# sensor-test.net
KiCad netlist of a schematic drawn in EAGLE
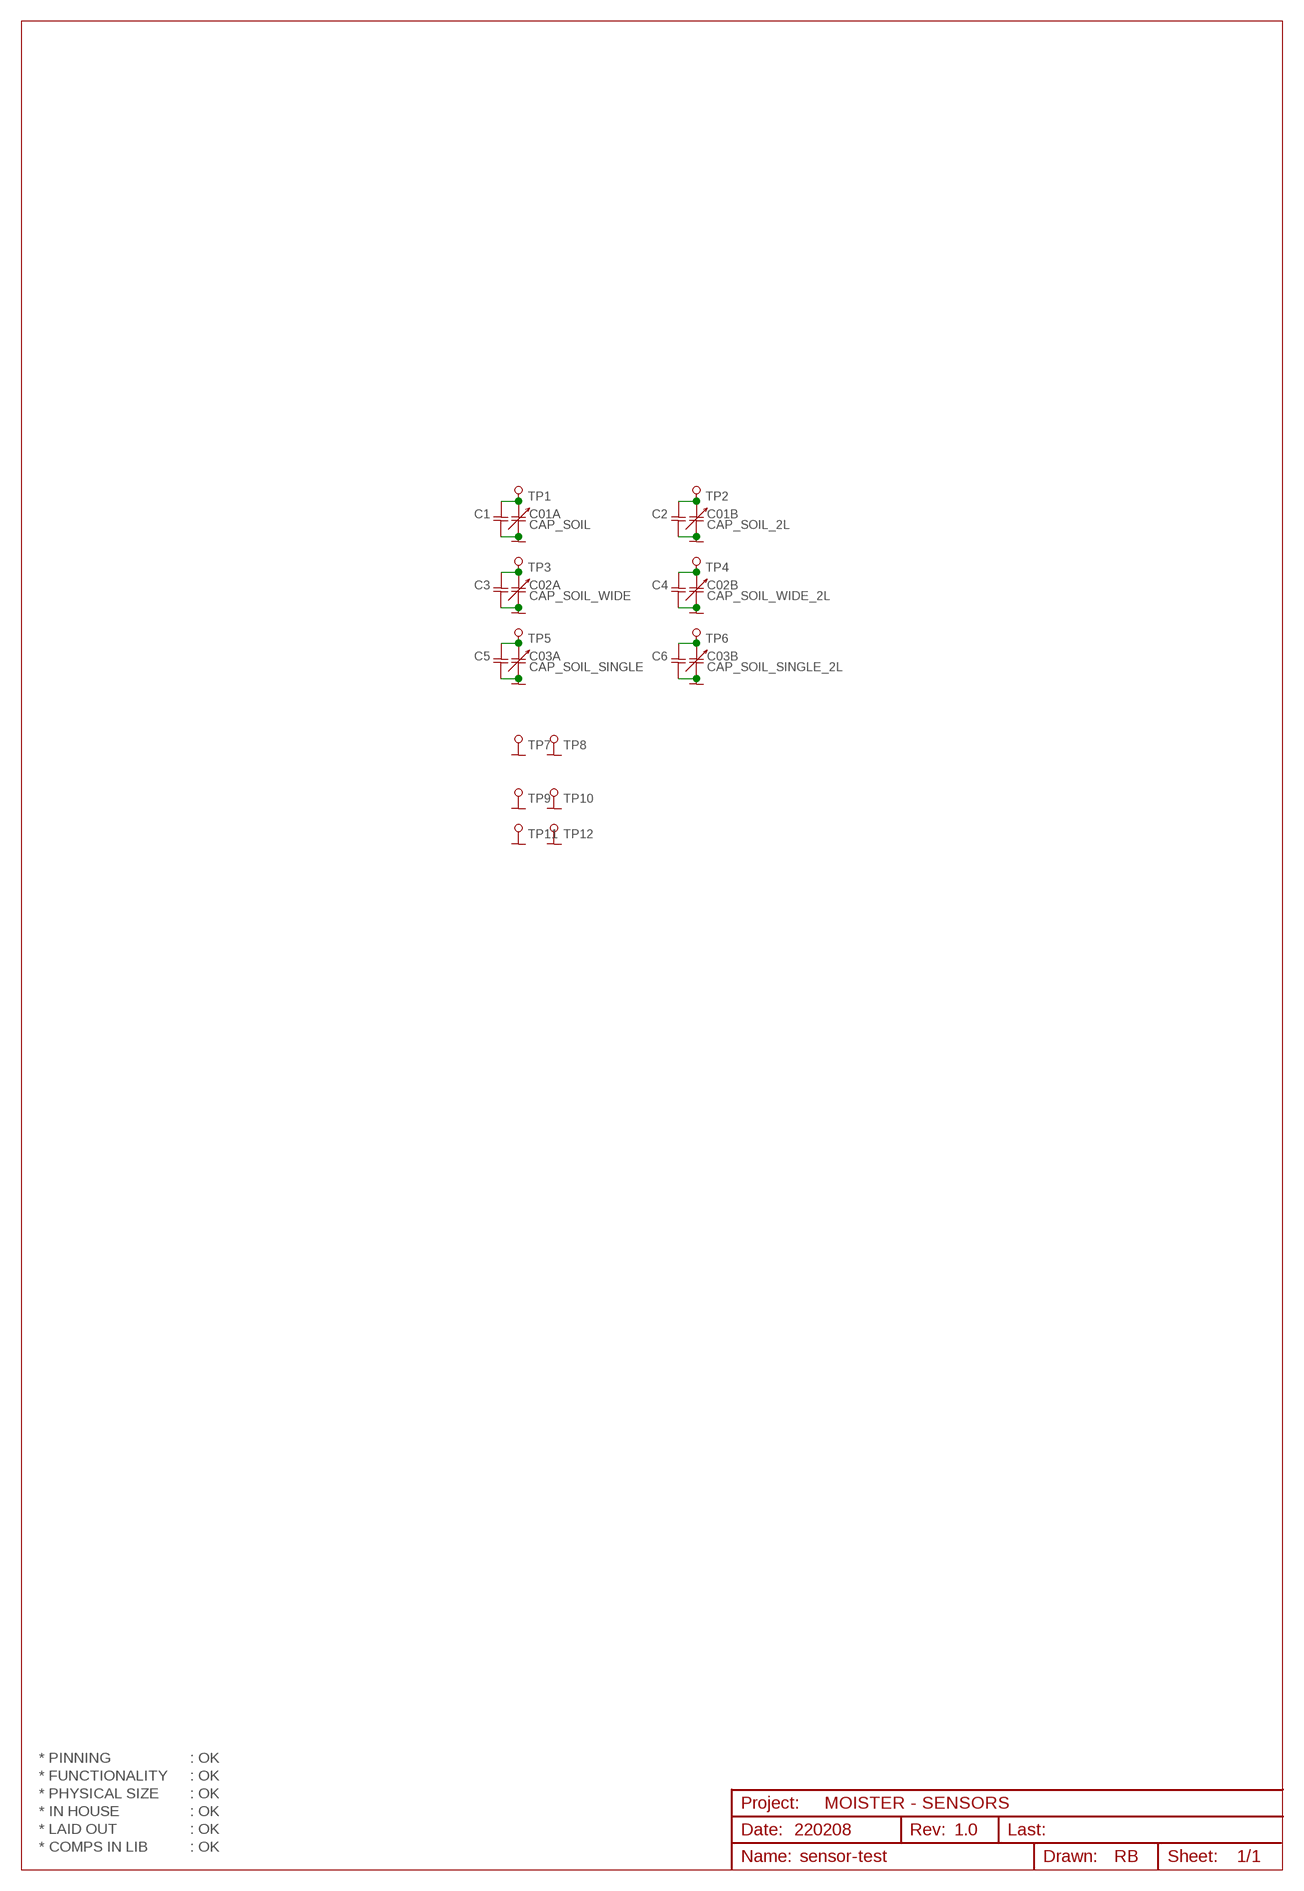
[diagram p0: schematic, sheet 1]

(export (version "E")
  (design (tool "Eeschema 10.0.6"))
  (components
    (comp (ref "C1")
      (value "CAP0805")
      (footprint "eagle-import:CAP0805")
      (libsource (lib "eagle-import") (part "CAP0805"))
    )
    (comp (ref "C01A")
      (value "CAP_SOIL")
      (footprint "eagle-import:CAP_SOIL")
      (libsource (lib "eagle-import") (part "CAP_SOIL"))
    )
    (comp (ref "C01B")
      (value "CAP_SOIL_2L")
      (footprint "eagle-import:CAP_SOIL_2LAYER")
      (libsource (lib "eagle-import") (part "CAP_SOIL_2LAYER"))
    )
    (comp (ref "C2")
      (value "CAP0805")
      (footprint "eagle-import:CAP0805")
      (libsource (lib "eagle-import") (part "CAP0805"))
    )
    (comp (ref "C02A")
      (value "CAP_SOIL_WIDE")
      (footprint "eagle-import:CAP_SOIL_WIDE")
      (libsource (lib "eagle-import") (part "CAP_SOIL_WIDE"))
    )
    (comp (ref "C02B")
      (value "CAP_SOIL_WIDE_2L")
      (footprint "eagle-import:CAP_SOIL_WIDE_2LAYER")
      (libsource (lib "eagle-import") (part "CAP_SOIL_WIDE_2LAYER"))
    )
    (comp (ref "C3")
      (value "CAP0805")
      (footprint "eagle-import:CAP0805")
      (libsource (lib "eagle-import") (part "CAP0805"))
    )
    (comp (ref "C03A")
      (value "CAP_SOIL_SINGLE")
      (footprint "eagle-import:CAP_SOIL_SINGLE")
      (libsource (lib "eagle-import") (part "CAP_SOIL_SINGLE"))
    )
    (comp (ref "C03B")
      (value "CAP_SOIL_SINGLE_2L")
      (footprint "eagle-import:CAP_SOIL_SINGLE_2LAYER")
      (libsource (lib "eagle-import") (part "CAP_SOIL_SINGLE_2LAYER"))
    )
    (comp (ref "C4")
      (value "CAP0805")
      (footprint "eagle-import:CAP0805")
      (libsource (lib "eagle-import") (part "CAP0805"))
    )
    (comp (ref "C5")
      (value "CAP0805")
      (footprint "eagle-import:CAP0805")
      (libsource (lib "eagle-import") (part "CAP0805"))
    )
    (comp (ref "C6")
      (value "CAP0805")
      (footprint "eagle-import:CAP0805")
      (libsource (lib "eagle-import") (part "CAP0805"))
    )
    (comp (ref "TP1")
      (value "PIN_TEST")
      (footprint "eagle-import:HOLE_PTH_0.8MM")
      (libsource (lib "eagle-import") (part "PIN_TEST"))
    )
    (comp (ref "TP2")
      (value "PIN_TEST")
      (footprint "eagle-import:HOLE_PTH_0.8MM")
      (libsource (lib "eagle-import") (part "PIN_TEST"))
    )
    (comp (ref "TP3")
      (value "PIN_TEST")
      (footprint "eagle-import:HOLE_PTH_0.8MM")
      (libsource (lib "eagle-import") (part "PIN_TEST"))
    )
    (comp (ref "TP4")
      (value "PIN_TEST")
      (footprint "eagle-import:HOLE_PTH_0.8MM")
      (libsource (lib "eagle-import") (part "PIN_TEST"))
    )
    (comp (ref "TP5")
      (value "PIN_TEST")
      (footprint "eagle-import:HOLE_PTH_0.8MM")
      (libsource (lib "eagle-import") (part "PIN_TEST"))
    )
    (comp (ref "TP6")
      (value "PIN_TEST")
      (footprint "eagle-import:HOLE_PTH_0.8MM")
      (libsource (lib "eagle-import") (part "PIN_TEST"))
    )
    (comp (ref "TP7")
      (value "PIN_TEST")
      (footprint "eagle-import:HOLE_PTH_0.8MM")
      (libsource (lib "eagle-import") (part "PIN_TEST"))
    )
    (comp (ref "TP8")
      (value "PIN_TEST")
      (footprint "eagle-import:HOLE_PTH_0.8MM")
      (libsource (lib "eagle-import") (part "PIN_TEST"))
    )
    (comp (ref "TP9")
      (value "PIN_TEST")
      (footprint "eagle-import:HOLE_PTH_0.8MM")
      (libsource (lib "eagle-import") (part "PIN_TEST"))
    )
    (comp (ref "TP10")
      (value "PIN_TEST")
      (footprint "eagle-import:HOLE_PTH_0.8MM")
      (libsource (lib "eagle-import") (part "PIN_TEST"))
    )
    (comp (ref "TP11")
      (value "PIN_TEST")
      (footprint "eagle-import:HOLE_PTH_0.8MM")
      (libsource (lib "eagle-import") (part "PIN_TEST"))
    )
    (comp (ref "TP12")
      (value "PIN_TEST")
      (footprint "eagle-import:HOLE_PTH_0.8MM")
      (libsource (lib "eagle-import") (part "PIN_TEST"))
    )
  )
  (nets
    (net (code "1") (name "GND") (class "Default")
      (node (ref "C01A") (pin "2") (pinfunction "2_2") (pintype "passive"))
      (node (ref "C01B") (pin "2") (pinfunction "2_2") (pintype "passive"))
      (node (ref "C01B") (pin "P$1") (pinfunction "2_P$1") (pintype "passive"))
      (node (ref "C02A") (pin "2") (pinfunction "2_2") (pintype "passive"))
      (node (ref "C02B") (pin "2") (pinfunction "2_2") (pintype "passive"))
      (node (ref "C02B") (pin "P$1") (pinfunction "2_P$1") (pintype "passive"))
      (node (ref "C03A") (pin "2") (pinfunction "2_2") (pintype "passive"))
      (node (ref "C03B") (pin "2") (pinfunction "2_2") (pintype "passive"))
      (node (ref "C1") (pin "2") (pinfunction "2_2") (pintype "passive"))
      (node (ref "C2") (pin "2") (pinfunction "2_2") (pintype "passive"))
      (node (ref "C3") (pin "2") (pinfunction "2_2") (pintype "passive"))
      (node (ref "C4") (pin "2") (pinfunction "2_2") (pintype "passive"))
      (node (ref "C5") (pin "2") (pinfunction "2_2") (pintype "passive"))
      (node (ref "C6") (pin "2") (pinfunction "2_2") (pintype "passive"))
      (node (ref "TP10") (pin "1") (pinfunction "P$1_1") (pintype "passive"))
      (node (ref "TP11") (pin "1") (pinfunction "P$1_1") (pintype "passive"))
      (node (ref "TP12") (pin "1") (pinfunction "P$1_1") (pintype "passive"))
      (node (ref "TP7") (pin "1") (pinfunction "P$1_1") (pintype "passive"))
      (node (ref "TP8") (pin "1") (pinfunction "P$1_1") (pintype "passive"))
      (node (ref "TP9") (pin "1") (pinfunction "P$1_1") (pintype "passive"))
    )
    (net (code "2") (name "Net-(TP1-P$1)") (class "Default")
      (node (ref "C01A") (pin "1") (pinfunction "1_1") (pintype "passive"))
      (node (ref "C1") (pin "1") (pinfunction "1_1") (pintype "passive"))
      (node (ref "TP1") (pin "1") (pinfunction "P$1_1") (pintype "passive"))
    )
    (net (code "3") (name "Net-(TP2-P$1)") (class "Default")
      (node (ref "C01B") (pin "1") (pinfunction "1_1") (pintype "passive"))
      (node (ref "C2") (pin "1") (pinfunction "1_1") (pintype "passive"))
      (node (ref "TP2") (pin "1") (pinfunction "P$1_1") (pintype "passive"))
    )
    (net (code "4") (name "Net-(TP3-P$1)") (class "Default")
      (node (ref "C02A") (pin "1") (pinfunction "1_1") (pintype "passive"))
      (node (ref "C3") (pin "1") (pinfunction "1_1") (pintype "passive"))
      (node (ref "TP3") (pin "1") (pinfunction "P$1_1") (pintype "passive"))
    )
    (net (code "5") (name "Net-(TP4-P$1)") (class "Default")
      (node (ref "C02B") (pin "1") (pinfunction "1_1") (pintype "passive"))
      (node (ref "C4") (pin "1") (pinfunction "1_1") (pintype "passive"))
      (node (ref "TP4") (pin "1") (pinfunction "P$1_1") (pintype "passive"))
    )
    (net (code "6") (name "Net-(TP5-P$1)") (class "Default")
      (node (ref "C03A") (pin "1") (pinfunction "1_1") (pintype "passive"))
      (node (ref "C5") (pin "1") (pinfunction "1_1") (pintype "passive"))
      (node (ref "TP5") (pin "1") (pinfunction "P$1_1") (pintype "passive"))
    )
    (net (code "7") (name "Net-(TP6-P$1)") (class "Default")
      (node (ref "C03B") (pin "1") (pinfunction "1_1") (pintype "passive"))
      (node (ref "C6") (pin "1") (pinfunction "1_1") (pintype "passive"))
      (node (ref "TP6") (pin "1") (pinfunction "P$1_1") (pintype "passive"))
    )
  )
)
